# Power.net
KiCad netlist of a schematic drawn in Altium Designer
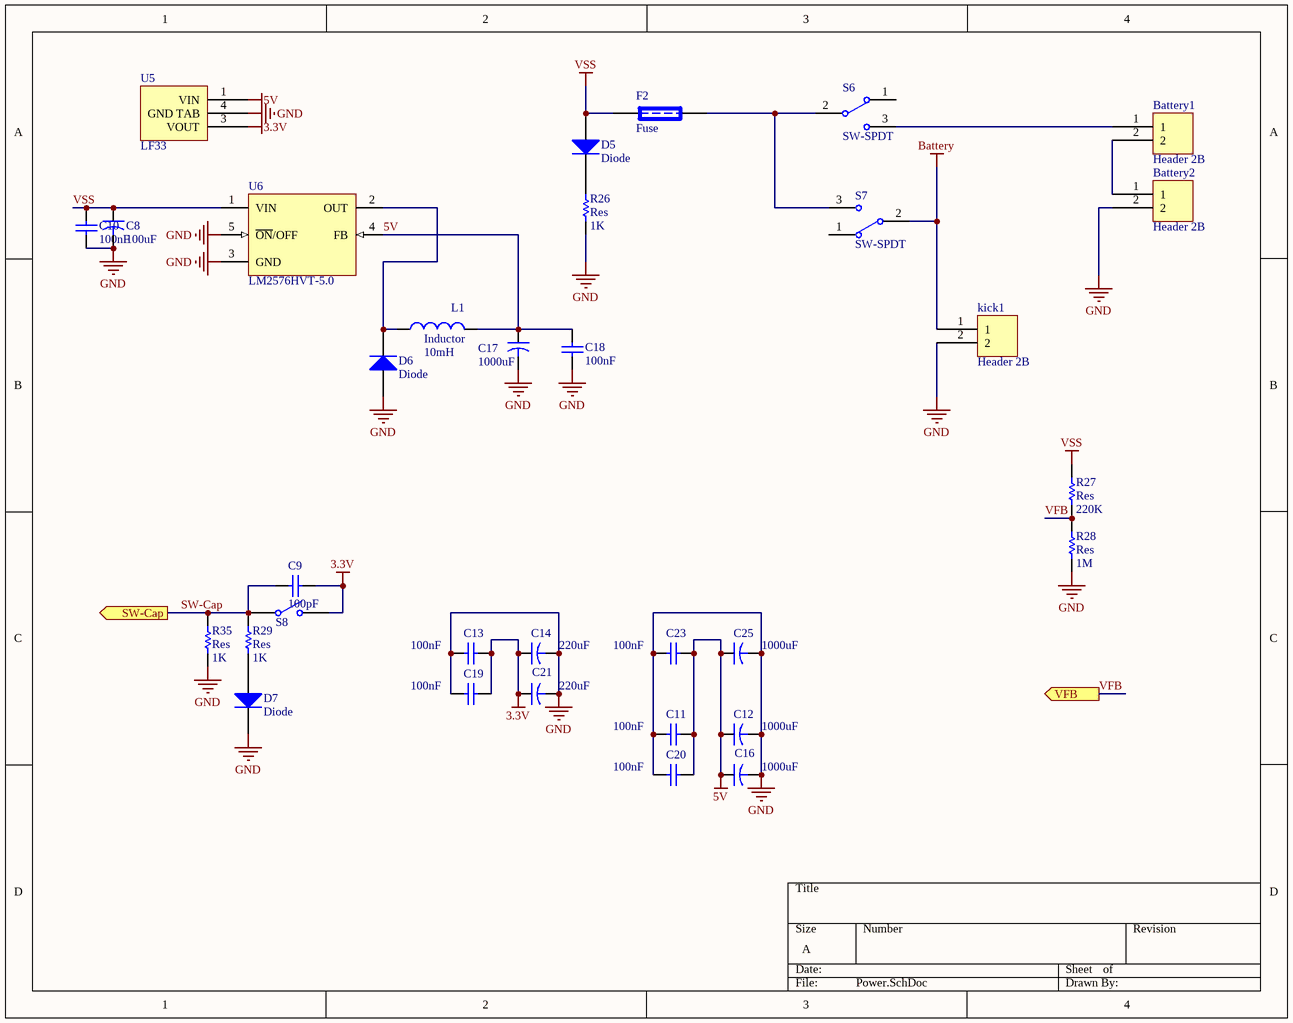
[diagram p0: Power.SchDoc]

(export (version "E")
  (design (tool "Eeschema 10.0.6"))
  (components
    (comp (ref "Battery1")
      (value "Header 2B")
      (footprint "BHDR1X2")
      (libsource (lib "KN2CLib") (part "Header 2B"))
    )
    (comp (ref "Battery2")
      (value "Header 2B")
      (footprint "BHDR1X2")
      (libsource (lib "KN2CLib") (part "Header 2B"))
    )
    (comp (ref "C8")
      (value "100uF")
      (footprint "Cap1000u-16")
      (description "Capacitor")
      (fields (field (name "Comment") "Cap_El") (field (name "PUBLISHER") "Altium Limited"))
      (libsource (lib "KN2CLib") (part "Cap_El"))
    )
    (comp (ref "C9")
      (value "100pF")
      (footprint "2012[0805]")
      (description "Capacitor")
      (fields (field (name "Comment") "Cap_UP") (field (name "PUBLISHER") "Altium Limited"))
      (libsource (lib "KN2CLib") (part "Cap_UP"))
    )
    (comp (ref "C10")
      (value "100nF")
      (footprint "2012[0805]")
      (description "Capacitor")
      (fields (field (name "Comment") "Cap_UP") (field (name "PUBLISHER") "Altium Limited"))
      (libsource (lib "KN2CLib") (part "Cap_UP"))
    )
    (comp (ref "C11")
      (value "100nF")
      (footprint "2012[0805]")
      (description "Capacitor")
      (fields (field (name "Comment") "Cap_UP") (field (name "PUBLISHER") "Altium Limited"))
      (libsource (lib "KN2CLib") (part "Cap_UP"))
    )
    (comp (ref "C12")
      (value "1000uF")
      (footprint "7343")
      (description "Capacitor")
      (fields (field (name "Comment") "Cap_El") (field (name "PUBLISHER") "Altium Limited"))
      (libsource (lib "KN2CLib") (part "Cap_El"))
    )
    (comp (ref "C13")
      (value "100nF")
      (footprint "2012[0805]")
      (description "Capacitor")
      (fields (field (name "Comment") "Cap_UP") (field (name "PUBLISHER") "Altium Limited"))
      (libsource (lib "KN2CLib") (part "Cap_UP"))
    )
    (comp (ref "C14")
      (value "220uF")
      (footprint "7343")
      (description "Capacitor")
      (fields (field (name "Comment") "Cap_El") (field (name "PUBLISHER") "Altium Limited"))
      (libsource (lib "KN2CLib") (part "Cap_El"))
    )
    (comp (ref "C16")
      (value "1000uF")
      (footprint "7343")
      (description "Capacitor")
      (fields (field (name "Comment") "Cap_El") (field (name "PUBLISHER") "Altium Limited"))
      (libsource (lib "KN2CLib") (part "Cap_El"))
    )
    (comp (ref "C17")
      (value "1000uF")
      (footprint "7343")
      (description "Capacitor")
      (fields (field (name "Comment") "Cap_El") (field (name "PUBLISHER") "Altium Limited"))
      (libsource (lib "KN2CLib") (part "Cap_El"))
    )
    (comp (ref "C18")
      (value "100nF")
      (footprint "2012[0805]")
      (description "Capacitor")
      (fields (field (name "Comment") "Cap_UP") (field (name "PUBLISHER") "Altium Limited"))
      (libsource (lib "KN2CLib") (part "Cap_UP"))
    )
    (comp (ref "C19")
      (value "100nF")
      (footprint "2012[0805]")
      (description "Capacitor")
      (fields (field (name "Comment") "Cap_UP") (field (name "PUBLISHER") "Altium Limited"))
      (libsource (lib "KN2CLib") (part "Cap_UP"))
    )
    (comp (ref "C20")
      (value "100nF")
      (footprint "2012[0805]")
      (description "Capacitor")
      (fields (field (name "Comment") "Cap_UP") (field (name "PUBLISHER") "Altium Limited"))
      (libsource (lib "KN2CLib") (part "Cap_UP"))
    )
    (comp (ref "C21")
      (value "220uF")
      (footprint "7343")
      (description "Capacitor")
      (fields (field (name "Comment") "Cap_El") (field (name "PUBLISHER") "Altium Limited"))
      (libsource (lib "KN2CLib") (part "Cap_El"))
    )
    (comp (ref "C23")
      (value "100nF")
      (footprint "2012[0805]")
      (description "Capacitor")
      (fields (field (name "Comment") "Cap_UP") (field (name "PUBLISHER") "Altium Limited"))
      (libsource (lib "KN2CLib") (part "Cap_UP"))
    )
    (comp (ref "C25")
      (value "1000uF")
      (footprint "7343")
      (description "Capacitor")
      (fields (field (name "Comment") "Cap_El") (field (name "PUBLISHER") "Altium Limited"))
      (libsource (lib "KN2CLib") (part "Cap_El"))
    )
    (comp (ref "D5")
      (value "Diode")
      (footprint "2012[0805]")
      (description "1 Amp General Purpose Rectifier")
      (fields (field (name "PUBLISHER") "Altium Limited"))
      (libsource (lib "KN2CLib") (part "Diode"))
    )
    (comp (ref "D6")
      (value "Diode")
      (footprint "US1M")
      (description "1 Amp General Purpose Rectifier")
      (fields (field (name "PUBLISHER") "Altium Limited"))
      (libsource (lib "KN2CLib") (part "Diode"))
    )
    (comp (ref "D7")
      (value "Diode")
      (footprint "2012[0805]")
      (description "1 Amp General Purpose Rectifier")
      (fields (field (name "PUBLISHER") "Altium Limited"))
      (libsource (lib "KN2CLib") (part "Diode"))
    )
    (comp (ref "F2")
      (value "Fuse")
      (footprint "fuse kh")
      (fields (field (name "PUBLISHER") "Altium Limited"))
      (libsource (lib "KN2CLib") (part "Fuse"))
    )
    (comp (ref "kick1")
      (value "Header 2B")
      (footprint "BHDR1X2")
      (libsource (lib "KN2CLib") (part "Header 2B"))
    )
    (comp (ref "L1")
      (value "Inductor")
      (footprint "inductor")
      (fields (field (name "ALTIUM_VALUE") "10mH") (field (name "PUBLISHER") "Altium Limited"))
      (libsource (lib "KN2CLib") (part "Inductor"))
    )
    (comp (ref "R26")
      (value "Res")
      (footprint "2012[0805]")
      (description "Semiconductor Resistor")
      (fields (field (name "ALTIUM_VALUE") "1K") (field (name "PUBLISHER") "Altium Limited"))
      (libsource (lib "KN2CLib") (part "Res"))
    )
    (comp (ref "R27")
      (value "Res")
      (footprint "2012[0805]")
      (description "Semiconductor Resistor")
      (fields (field (name "ALTIUM_VALUE") "220K") (field (name "PUBLISHER") "Altium Limited"))
      (libsource (lib "KN2CLib") (part "Res"))
    )
    (comp (ref "R28")
      (value "Res")
      (footprint "2012[0805]")
      (description "Semiconductor Resistor")
      (fields (field (name "ALTIUM_VALUE") "1M") (field (name "PUBLISHER") "Altium Limited"))
      (libsource (lib "KN2CLib") (part "Res"))
    )
    (comp (ref "R29")
      (value "Res")
      (footprint "2012[0805]")
      (description "Semiconductor Resistor")
      (fields (field (name "ALTIUM_VALUE") "1K") (field (name "PUBLISHER") "Altium Limited"))
      (libsource (lib "KN2CLib") (part "Res"))
    )
    (comp (ref "R35")
      (value "Res")
      (footprint "2012[0805]")
      (description "Semiconductor Resistor")
      (fields (field (name "ALTIUM_VALUE") "1K") (field (name "PUBLISHER") "Altium Limited"))
      (libsource (lib "KN2CLib") (part "Res"))
    )
    (comp (ref "S6")
      (value "SW-SPDT")
      (footprint "KEYKHRAB")
      (description "SPDT Subminiature Toggle Switch, Right Angle Mounting, Vertical Actuation")
      (fields (field (name "PUBLISHER") "Altium Limited"))
      (libsource (lib "KN2CLib") (part "SW-SPDT"))
    )
    (comp (ref "S7")
      (value "SW-SPDT")
      (footprint "KEYKHRAB")
      (description "SPDT Subminiature Toggle Switch, Right Angle Mounting, Vertical Actuation")
      (fields (field (name "PUBLISHER") "Altium Limited"))
      (libsource (lib "KN2CLib") (part "SW-SPDT"))
    )
    (comp (ref "S8")
      (value "SW-SPST")
      (footprint "push button B")
      (description "Single-Pole, Single-Throw Switch")
      (fields (field (name "PUBLISHER") "Altium Limited"))
      (libsource (lib "KN2CLib") (part "SW-SPST"))
    )
    (comp (ref "U5") (value "LF33") (footprint "D-PACK") (libsource (lib "KN2CLib") (part "7805")))
    (comp (ref "U6")
      (value "LM2576HVT-5.0")
      (footprint "T05A")
      (description "SIMPLE SWITCHER; 3A Step-Down Voltage Regulator")
      (fields
        (field (name "MANUFACTURER") "National Semiconductor")
        (field (name "DIGIKEYPARTNUMBER") "LM2576HVT-5.0-ND")
        (field (name "PUBLISHER") "Altium Limited")
      )
      (libsource (lib "NSC Switcher") (part "LM2576HVT-5.0"))
    )
  )
  (nets
    (net (code "1") (name "/SW-Cap") (class "Default")
      (node (ref "C9") (pin "1") (pinfunction "1_1") (pintype "passive"))
      (node (ref "R29") (pin "2") (pinfunction "2_2") (pintype "passive"))
      (node (ref "R35") (pin "2") (pinfunction "2_2") (pintype "passive"))
      (node (ref "S8") (pin "1") (pinfunction "COMMON_1") (pintype "passive"))
    )
    (net (code "2") (name "/VFB") (class "Default")
      (node (ref "R27") (pin "1") (pinfunction "1_1") (pintype "passive"))
      (node (ref "R28") (pin "2") (pinfunction "2_2") (pintype "passive"))
    )
    (net (code "3") (name "3.3V") (class "Default")
      (node (ref "C13") (pin "2") (pinfunction "2_2") (pintype "passive"))
      (node (ref "C14") (pin "1") (pinfunction "1_1") (pintype "passive"))
      (node (ref "C19") (pin "2") (pinfunction "2_2") (pintype "passive"))
      (node (ref "C21") (pin "1") (pinfunction "1_1") (pintype "passive"))
      (node (ref "C9") (pin "2") (pinfunction "2_2") (pintype "passive"))
      (node (ref "S8") (pin "2") (pinfunction "NO_2") (pintype "passive"))
      (node (ref "U5") (pin "3") (pinfunction "VOUT_3") (pintype "passive"))
    )
    (net (code "4") (name "5V") (class "Default")
      (node (ref "C11") (pin "2") (pinfunction "2_2") (pintype "passive"))
      (node (ref "C12") (pin "1") (pinfunction "1_1") (pintype "passive"))
      (node (ref "C16") (pin "1") (pinfunction "1_1") (pintype "passive"))
      (node (ref "C17") (pin "1") (pinfunction "1_1") (pintype "passive"))
      (node (ref "C18") (pin "2") (pinfunction "2_2") (pintype "passive"))
      (node (ref "C20") (pin "2") (pinfunction "2_2") (pintype "passive"))
      (node (ref "C23") (pin "2") (pinfunction "2_2") (pintype "passive"))
      (node (ref "C25") (pin "1") (pinfunction "1_1") (pintype "passive"))
      (node (ref "L1") (pin "2") (pinfunction "2_2") (pintype "passive"))
      (node (ref "U5") (pin "1") (pinfunction "VIN_1") (pintype "passive"))
      (node (ref "U6") (pin "4") (pinfunction "FB_4") (pintype "input"))
    )
    (net (code "5") (name "Battery") (class "Default")
      (node (ref "S7") (pin "2") (pinfunction "2_2") (pintype "passive"))
      (node (ref "kick1") (pin "1") (pinfunction "1_1") (pintype "passive"))
    )
    (net (code "6") (name "GND") (class "Default")
      (node (ref "Battery2") (pin "2") (pinfunction "2_2") (pintype "passive"))
      (node (ref "C10") (pin "1") (pinfunction "1_1") (pintype "passive"))
      (node (ref "C11") (pin "1") (pinfunction "1_1") (pintype "passive"))
      (node (ref "C12") (pin "2") (pinfunction "2_2") (pintype "passive"))
      (node (ref "C13") (pin "1") (pinfunction "1_1") (pintype "passive"))
      (node (ref "C14") (pin "2") (pinfunction "2_2") (pintype "passive"))
      (node (ref "C16") (pin "2") (pinfunction "2_2") (pintype "passive"))
      (node (ref "C17") (pin "2") (pinfunction "2_2") (pintype "passive"))
      (node (ref "C18") (pin "1") (pinfunction "1_1") (pintype "passive"))
      (node (ref "C19") (pin "1") (pinfunction "1_1") (pintype "passive"))
      (node (ref "C20") (pin "1") (pinfunction "1_1") (pintype "passive"))
      (node (ref "C21") (pin "2") (pinfunction "2_2") (pintype "passive"))
      (node (ref "C23") (pin "1") (pinfunction "1_1") (pintype "passive"))
      (node (ref "C25") (pin "2") (pinfunction "2_2") (pintype "passive"))
      (node (ref "C8") (pin "2") (pinfunction "2_2") (pintype "passive"))
      (node (ref "D6") (pin "1") (pinfunction "A_1") (pintype "passive"))
      (node (ref "D7") (pin "2") (pinfunction "K_2") (pintype "passive"))
      (node (ref "R26") (pin "1") (pinfunction "1_1") (pintype "passive"))
      (node (ref "R28") (pin "1") (pinfunction "1_1") (pintype "passive"))
      (node (ref "R35") (pin "1") (pinfunction "1_1") (pintype "passive"))
      (node (ref "U5") (pin "4") (pinfunction "GND_TAB_4") (pintype "passive"))
      (node (ref "U6") (pin "3") (pinfunction "GND_3") (pintype "power_in"))
      (node (ref "U6") (pin "5") (pinfunction "~{ON}/OFF_5") (pintype "input"))
      (node (ref "kick1") (pin "2") (pinfunction "2_2") (pintype "passive"))
    )
    (net (code "7") (name "Net-(Battery1-Pad2)") (class "Default")
      (node (ref "Battery1") (pin "2") (pinfunction "2_2") (pintype "passive"))
      (node (ref "Battery2") (pin "1") (pinfunction "1_1") (pintype "passive"))
    )
    (net (code "8") (name "Net-(D5-K)") (class "Default")
      (node (ref "D5") (pin "2") (pinfunction "K_2") (pintype "passive"))
      (node (ref "R26") (pin "2") (pinfunction "2_2") (pintype "passive"))
    )
    (net (code "9") (name "Net-(D6-K)") (class "Default")
      (node (ref "D6") (pin "2") (pinfunction "K_2") (pintype "passive"))
      (node (ref "L1") (pin "1") (pinfunction "1_1") (pintype "passive"))
      (node (ref "U6") (pin "2") (pinfunction "OUT_2") (pintype "power_in"))
    )
    (net (code "10") (name "Net-(D7-A)") (class "Default")
      (node (ref "D7") (pin "1") (pinfunction "A_1") (pintype "passive"))
      (node (ref "R29") (pin "1") (pinfunction "1_1") (pintype "passive"))
    )
    (net (code "11") (name "Net-(S6-1)") (class "Default")
      (node (ref "Battery1") (pin "1") (pinfunction "1_1") (pintype "passive"))
      (node (ref "S6") (pin "3") (pinfunction "1_3") (pintype "passive"))
    )
    (net (code "12") (name "Net-(S7-1)") (class "Default")
      (node (ref "F2") (pin "2") (pinfunction "2_2") (pintype "passive"))
      (node (ref "S6") (pin "2") (pinfunction "2_2") (pintype "passive"))
      (node (ref "S7") (pin "3") (pinfunction "1_3") (pintype "passive"))
    )
    (net (code "13") (name "VSS") (class "Default")
      (node (ref "C10") (pin "2") (pinfunction "2_2") (pintype "passive"))
      (node (ref "C8") (pin "1") (pinfunction "1_1") (pintype "passive"))
      (node (ref "D5") (pin "1") (pinfunction "A_1") (pintype "passive"))
      (node (ref "F2") (pin "1") (pinfunction "1_1") (pintype "passive"))
      (node (ref "R27") (pin "2") (pinfunction "2_2") (pintype "passive"))
      (node (ref "U6") (pin "1") (pinfunction "VIN_1") (pintype "power_in"))
    )
    (net (code "14") (name "unconnected-(S6-3-Pad1)") (class "Default")
      (node (ref "S6") (pin "1") (pinfunction "3_1") (pintype "passive"))
    )
    (net (code "15") (name "unconnected-(S7-3-Pad1)") (class "Default")
      (node (ref "S7") (pin "1") (pinfunction "3_1") (pintype "passive"))
    )
  )
)
